# untitled.net
KiCad netlist of a schematic drawn in EAGLE
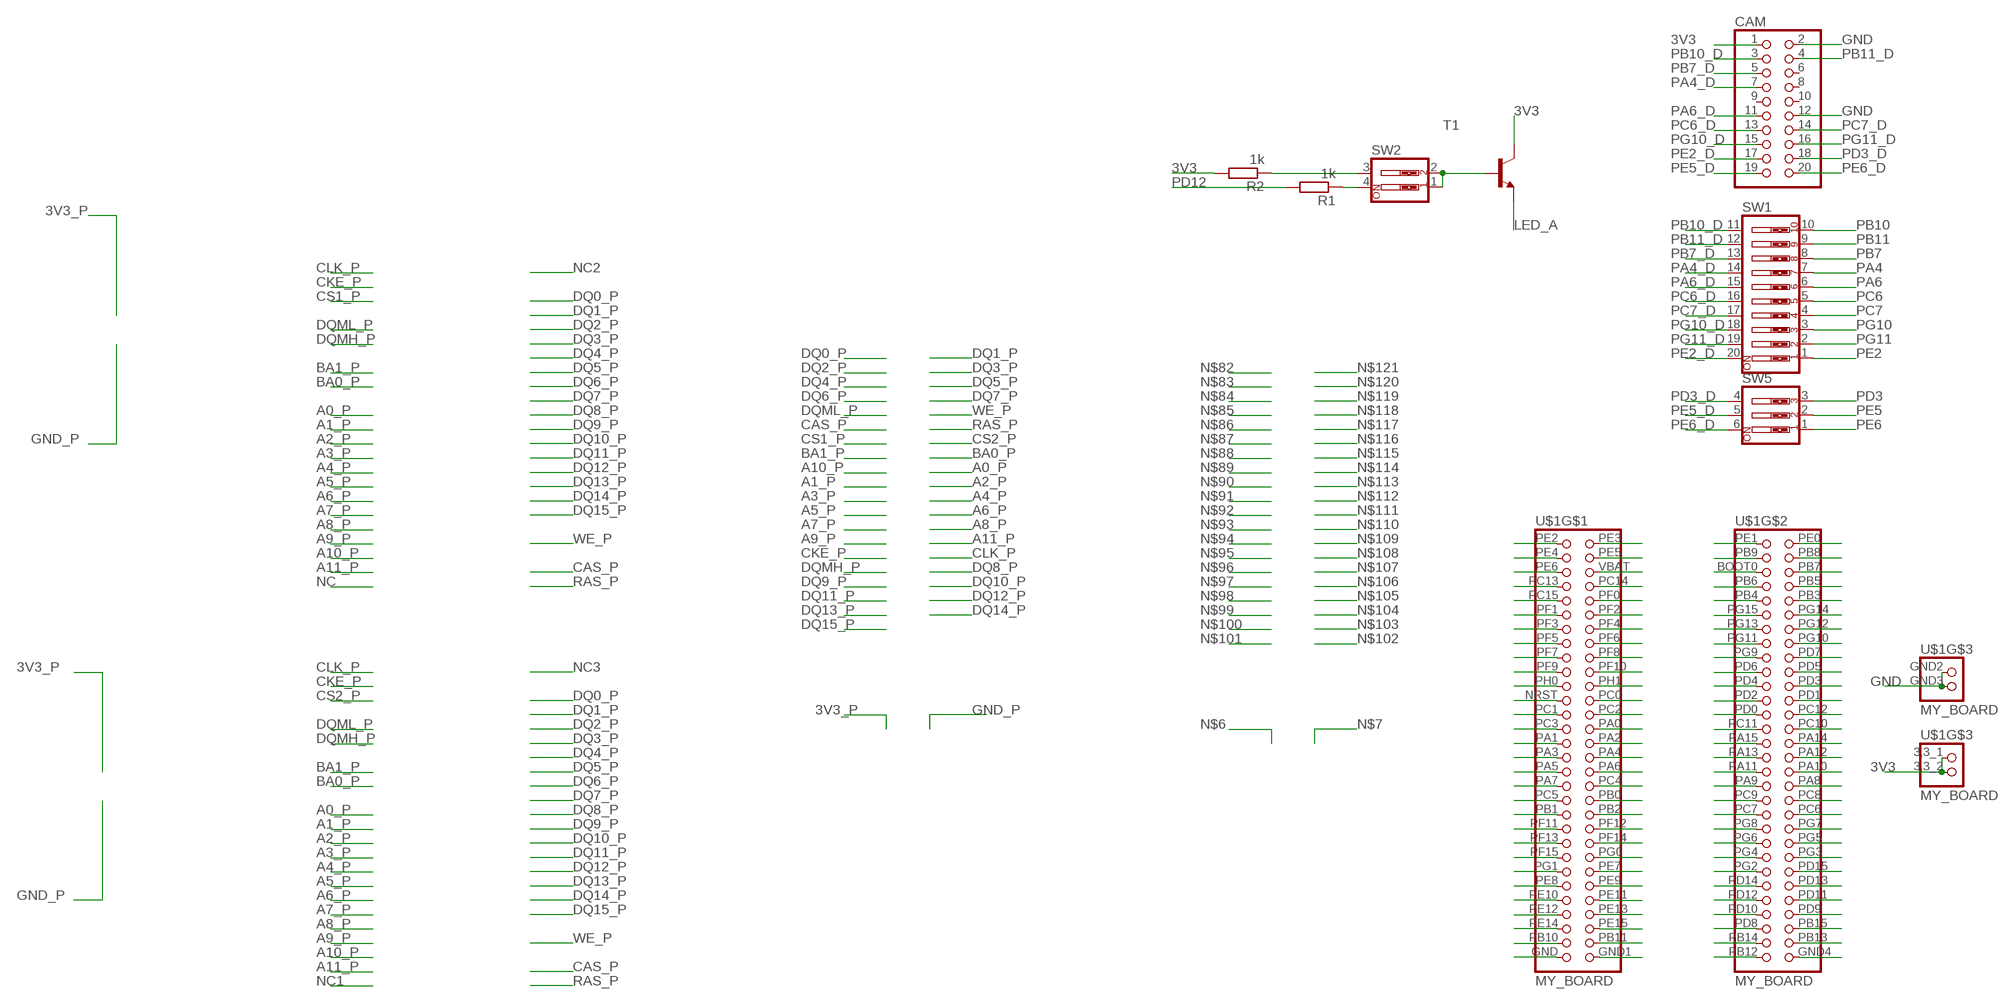
[diagram p0: schematic, sheet 1, part 1 of 2]
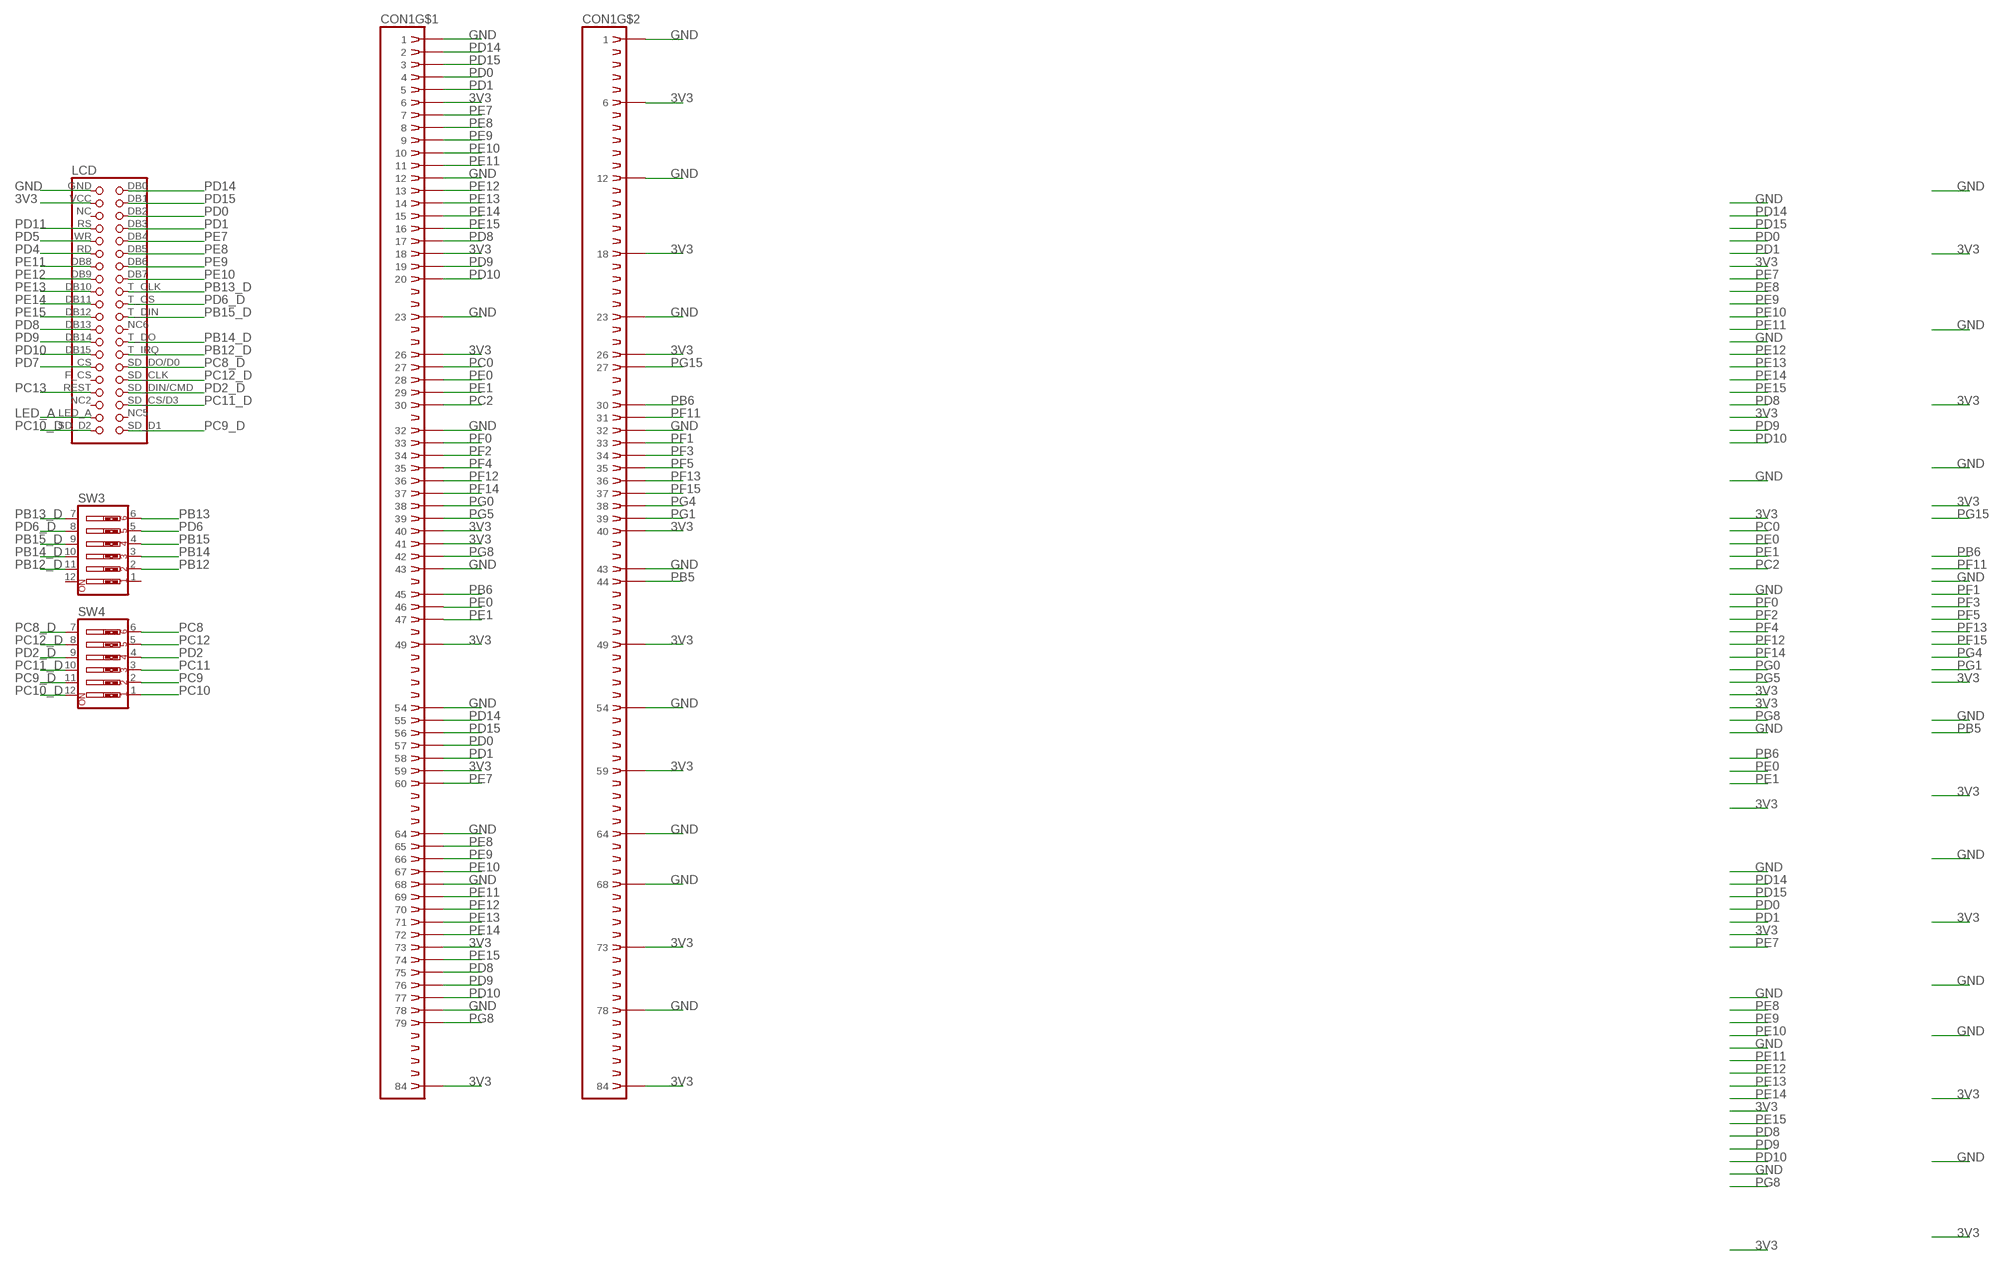
[diagram p1: schematic, sheet 1, part 2 of 2]

(export (version "E")
  (design (tool "Eeschema 10.0.6"))
  (components
    (comp (ref "CAM")
      (value "PINHD-2X10")
      (footprint "eagle-import:2X10")
      (libsource (lib "eagle-import") (part "PINHD-2X10"))
    )
    (comp (ref "CON1")
      (value "DIMM168")
      (footprint "eagle-import:390052-4")
      (libsource (lib "eagle-import") (part "DIMM168"))
    )
    (comp (ref "LCD")
      (value "LCD320QVBLCD320QVB")
      (footprint "eagle-import:2X20")
      (libsource (lib "eagle-import") (part "LCD320QVBLCD320QVB"))
    )
    (comp (ref "R1")
      (value "1k")
      (footprint "eagle-import:0204_5")
      (libsource (lib "eagle-import") (part "R-EU_0204/5"))
    )
    (comp (ref "R2")
      (value "1k")
      (footprint "eagle-import:0204_5")
      (libsource (lib "eagle-import") (part "R-EU_0204/5"))
    )
    (comp (ref "SW1")
      (value "SW_DIP-10")
      (footprint "eagle-import:EDG-10")
      (libsource (lib "eagle-import") (part "SW_DIP-10"))
    )
    (comp (ref "SW2")
      (value "SW_DIP-2")
      (footprint "eagle-import:EDG-02")
      (libsource (lib "eagle-import") (part "SW_DIP-2"))
    )
    (comp (ref "SW3")
      (value "SW_DIP-6")
      (footprint "eagle-import:EDG-06")
      (libsource (lib "eagle-import") (part "SW_DIP-6"))
    )
    (comp (ref "SW4")
      (value "SW_DIP-6")
      (footprint "eagle-import:EDG-06")
      (libsource (lib "eagle-import") (part "SW_DIP-6"))
    )
    (comp (ref "SW5")
      (value "SW_DIP-3")
      (footprint "eagle-import:EDG-03")
      (libsource (lib "eagle-import") (part "SW_DIP-3"))
    )
    (comp (ref "T1")
      (value "BC337-NPN-TO92-CBE")
      (footprint "eagle-import:TO92-CBE")
      (libsource (lib "eagle-import") (part "-NPN-TO92-CBEBC337"))
    )
    (comp (ref "U$1")
      (value "MY_BOARD")
      (footprint "eagle-import:MY_BOARD")
      (libsource (lib "eagle-import") (part "MY_BOARD"))
    )
  )
  (nets
    (net (code "1") (name "/3V3") (class "Default")
      (node (ref "CAM") (pin "1") (pinfunction "1_1") (pintype "passive"))
      (node (ref "CON1") (pin "102") (pinfunction "18_102") (pintype "passive"))
      (node (ref "CON1") (pin "110") (pinfunction "26_110") (pintype "passive"))
      (node (ref "CON1") (pin "124") (pinfunction "40_124") (pintype "passive"))
      (node (ref "CON1") (pin "133") (pinfunction "49_133") (pintype "passive"))
      (node (ref "CON1") (pin "143") (pinfunction "59_143") (pintype "passive"))
      (node (ref "CON1") (pin "157") (pinfunction "73_157") (pintype "passive"))
      (node (ref "CON1") (pin "168") (pinfunction "84_168") (pintype "passive"))
      (node (ref "CON1") (pin "18") (pinfunction "18_18") (pintype "passive"))
      (node (ref "CON1") (pin "26") (pinfunction "26_26") (pintype "passive"))
      (node (ref "CON1") (pin "40") (pinfunction "40_40") (pintype "passive"))
      (node (ref "CON1") (pin "41") (pinfunction "41_41") (pintype "passive"))
      (node (ref "CON1") (pin "49") (pinfunction "49_49") (pintype "passive"))
      (node (ref "CON1") (pin "59") (pinfunction "59_59") (pintype "passive"))
      (node (ref "CON1") (pin "6") (pinfunction "6_6") (pintype "passive"))
      (node (ref "CON1") (pin "73") (pinfunction "73_73") (pintype "passive"))
      (node (ref "CON1") (pin "84") (pinfunction "84_84") (pintype "passive"))
      (node (ref "CON1") (pin "90") (pinfunction "6_90") (pintype "passive"))
      (node (ref "LCD") (pin "VCC") (pinfunction "3_VCC") (pintype "passive"))
      (node (ref "R2") (pin "2") (pinfunction "2_2") (pintype "passive"))
      (node (ref "T1") (pin "C") (pinfunction "C_C") (pintype "passive"))
      (node (ref "U$1") (pin "3,3_1") (pinfunction "1_3,3_1") (pintype "passive"))
      (node (ref "U$1") (pin "3,3_2") (pinfunction "2_3,3_2") (pintype "passive"))
    )
    (net (code "40") (name "/GND") (class "Default")
      (node (ref "CAM") (pin "12") (pinfunction "12_12") (pintype "passive"))
      (node (ref "CAM") (pin "2") (pinfunction "2_2") (pintype "passive"))
      (node (ref "CON1") (pin "1") (pinfunction "1_1") (pintype "passive"))
      (node (ref "CON1") (pin "107") (pinfunction "23_107") (pintype "passive"))
      (node (ref "CON1") (pin "116") (pinfunction "32_116") (pintype "passive"))
      (node (ref "CON1") (pin "12") (pinfunction "12_12") (pintype "passive"))
      (node (ref "CON1") (pin "127") (pinfunction "43_127") (pintype "passive"))
      (node (ref "CON1") (pin "138") (pinfunction "54_138") (pintype "passive"))
      (node (ref "CON1") (pin "148") (pinfunction "64_148") (pintype "passive"))
      (node (ref "CON1") (pin "152") (pinfunction "68_152") (pintype "passive"))
      (node (ref "CON1") (pin "162") (pinfunction "78_162") (pintype "passive"))
      (node (ref "CON1") (pin "23") (pinfunction "23_23") (pintype "passive"))
      (node (ref "CON1") (pin "32") (pinfunction "32_32") (pintype "passive"))
      (node (ref "CON1") (pin "43") (pinfunction "43_43") (pintype "passive"))
      (node (ref "CON1") (pin "54") (pinfunction "54_54") (pintype "passive"))
      (node (ref "CON1") (pin "64") (pinfunction "64_64") (pintype "passive"))
      (node (ref "CON1") (pin "68") (pinfunction "68_68") (pintype "passive"))
      (node (ref "CON1") (pin "78") (pinfunction "78_78") (pintype "passive"))
      (node (ref "CON1") (pin "85") (pinfunction "1_85") (pintype "passive"))
      (node (ref "CON1") (pin "96") (pinfunction "12_96") (pintype "passive"))
      (node (ref "LCD") (pin "GND") (pinfunction "1_GND") (pintype "passive"))
      (node (ref "U$1") (pin "GND") (pinfunction "59_GND") (pintype "passive"))
      (node (ref "U$1") (pin "GND1") (pinfunction "60_GND1") (pintype "passive"))
      (node (ref "U$1") (pin "GND2") (pinfunction "3_GND2") (pintype "passive"))
      (node (ref "U$1") (pin "GND3") (pinfunction "4_GND3") (pintype "passive"))
      (node (ref "U$1") (pin "GND4") (pinfunction "60_GND4") (pintype "passive"))
    )
    (net (code "42") (name "/LED_A") (class "Default")
      (node (ref "LCD") (pin "LED_A") (pinfunction "37_LED_A") (pintype "passive"))
      (node (ref "T1") (pin "E") (pinfunction "E_E") (pintype "passive"))
    )
    (net (code "88") (name "/PA4") (class "Default")
      (node (ref "SW1") (pin "7") (pinfunction "7_7") (pintype "passive"))
      (node (ref "U$1") (pin "PA4") (pinfunction "32_PA4") (pintype "passive"))
    )
    (net (code "89") (name "/PA4_D") (class "Default")
      (node (ref "CAM") (pin "7") (pinfunction "7_7") (pintype "passive"))
      (node (ref "SW1") (pin "14") (pinfunction "14_14") (pintype "passive"))
    )
    (net (code "90") (name "/PA6") (class "Default")
      (node (ref "SW1") (pin "6") (pinfunction "6_6") (pintype "passive"))
      (node (ref "U$1") (pin "PA6") (pinfunction "34_PA6") (pintype "passive"))
    )
    (net (code "91") (name "/PA6_D") (class "Default")
      (node (ref "CAM") (pin "11") (pinfunction "11_11") (pintype "passive"))
      (node (ref "SW1") (pin "15") (pinfunction "15_15") (pintype "passive"))
    )
    (net (code "92") (name "/PB5") (class "Default")
      (node (ref "CON1") (pin "128") (pinfunction "44_128") (pintype "passive"))
      (node (ref "U$1") (pin "PB5") (pinfunction "8_PB5") (pintype "passive"))
    )
    (net (code "93") (name "/PB6") (class "Default")
      (node (ref "CON1") (pin "114") (pinfunction "30_114") (pintype "passive"))
      (node (ref "CON1") (pin "45") (pinfunction "45_45") (pintype "passive"))
      (node (ref "U$1") (pin "PB6") (pinfunction "7_PB6") (pintype "passive"))
    )
    (net (code "94") (name "/PB7") (class "Default")
      (node (ref "SW1") (pin "8") (pinfunction "8_8") (pintype "passive"))
      (node (ref "U$1") (pin "PB7") (pinfunction "6_PB7") (pintype "passive"))
    )
    (net (code "95") (name "/PB7_D") (class "Default")
      (node (ref "CAM") (pin "5") (pinfunction "5_5") (pintype "passive"))
      (node (ref "SW1") (pin "13") (pinfunction "13_13") (pintype "passive"))
    )
    (net (code "96") (name "/PB10") (class "Default")
      (node (ref "SW1") (pin "10") (pinfunction "10_10") (pintype "passive"))
      (node (ref "U$1") (pin "PB10") (pinfunction "57_PB10") (pintype "passive"))
    )
    (net (code "97") (name "/PB10_D") (class "Default")
      (node (ref "CAM") (pin "3") (pinfunction "3_3") (pintype "passive"))
      (node (ref "SW1") (pin "11") (pinfunction "11_11") (pintype "passive"))
    )
    (net (code "98") (name "/PB11") (class "Default")
      (node (ref "SW1") (pin "9") (pinfunction "9_9") (pintype "passive"))
      (node (ref "U$1") (pin "PB11") (pinfunction "58_PB11") (pintype "passive"))
    )
    (net (code "99") (name "/PB11_D") (class "Default")
      (node (ref "CAM") (pin "4") (pinfunction "4_4") (pintype "passive"))
      (node (ref "SW1") (pin "12") (pinfunction "12_12") (pintype "passive"))
    )
    (net (code "100") (name "/PB12") (class "Default")
      (node (ref "SW3") (pin "2") (pinfunction "2_2") (pintype "passive"))
      (node (ref "U$1") (pin "PB12") (pinfunction "59_PB12") (pintype "passive"))
    )
    (net (code "101") (name "/PB12_D") (class "Default")
      (node (ref "LCD") (pin "T_IRQ") (pinfunction "28_T_IRQ") (pintype "passive"))
      (node (ref "SW3") (pin "11") (pinfunction "11_11") (pintype "passive"))
    )
    (net (code "102") (name "/PB13") (class "Default")
      (node (ref "SW3") (pin "6") (pinfunction "6_6") (pintype "passive"))
      (node (ref "U$1") (pin "PB13") (pinfunction "58_PB13") (pintype "passive"))
    )
    (net (code "103") (name "/PB13_D") (class "Default")
      (node (ref "LCD") (pin "T_CLK") (pinfunction "18_T_CLK") (pintype "passive"))
      (node (ref "SW3") (pin "7") (pinfunction "7_7") (pintype "passive"))
    )
    (net (code "104") (name "/PB14") (class "Default")
      (node (ref "SW3") (pin "3") (pinfunction "3_3") (pintype "passive"))
      (node (ref "U$1") (pin "PB14") (pinfunction "57_PB14") (pintype "passive"))
    )
    (net (code "105") (name "/PB14_D") (class "Default")
      (node (ref "LCD") (pin "T_DO") (pinfunction "26_T_DO") (pintype "passive"))
      (node (ref "SW3") (pin "10") (pinfunction "10_10") (pintype "passive"))
    )
    (net (code "106") (name "/PB15") (class "Default")
      (node (ref "SW3") (pin "4") (pinfunction "4_4") (pintype "passive"))
      (node (ref "U$1") (pin "PB15") (pinfunction "56_PB15") (pintype "passive"))
    )
    (net (code "107") (name "/PB15_D") (class "Default")
      (node (ref "LCD") (pin "T_DIN") (pinfunction "22_T_DIN") (pintype "passive"))
      (node (ref "SW3") (pin "9") (pinfunction "9_9") (pintype "passive"))
    )
    (net (code "108") (name "/PC0") (class "Default")
      (node (ref "CON1") (pin "27") (pinfunction "27_27") (pintype "passive"))
      (node (ref "U$1") (pin "PC0") (pinfunction "24_PC0") (pintype "passive"))
    )
    (net (code "109") (name "/PC2") (class "Default")
      (node (ref "CON1") (pin "30") (pinfunction "30_30") (pintype "passive"))
      (node (ref "U$1") (pin "PC2") (pinfunction "26_PC2") (pintype "passive"))
    )
    (net (code "110") (name "/PC6") (class "Default")
      (node (ref "SW1") (pin "5") (pinfunction "5_5") (pintype "passive"))
      (node (ref "U$1") (pin "PC6") (pinfunction "40_PC6") (pintype "passive"))
    )
    (net (code "111") (name "/PC6_D") (class "Default")
      (node (ref "CAM") (pin "13") (pinfunction "13_13") (pintype "passive"))
      (node (ref "SW1") (pin "16") (pinfunction "16_16") (pintype "passive"))
    )
    (net (code "112") (name "/PC7") (class "Default")
      (node (ref "SW1") (pin "4") (pinfunction "4_4") (pintype "passive"))
      (node (ref "U$1") (pin "PC7") (pinfunction "39_PC7") (pintype "passive"))
    )
    (net (code "113") (name "/PC7_D") (class "Default")
      (node (ref "CAM") (pin "14") (pinfunction "14_14") (pintype "passive"))
      (node (ref "SW1") (pin "17") (pinfunction "17_17") (pintype "passive"))
    )
    (net (code "114") (name "/PC8") (class "Default")
      (node (ref "SW4") (pin "6") (pinfunction "6_6") (pintype "passive"))
      (node (ref "U$1") (pin "PC8") (pinfunction "38_PC8") (pintype "passive"))
    )
    (net (code "115") (name "/PC8_D") (class "Default")
      (node (ref "LCD") (pin "SD_DO/D0") (pinfunction "30_SD_DO/D0") (pintype "passive"))
      (node (ref "SW4") (pin "7") (pinfunction "7_7") (pintype "passive"))
    )
    (net (code "116") (name "/PC9") (class "Default")
      (node (ref "SW4") (pin "2") (pinfunction "2_2") (pintype "passive"))
      (node (ref "U$1") (pin "PC9") (pinfunction "37_PC9") (pintype "passive"))
    )
    (net (code "117") (name "/PC9_D") (class "Default")
      (node (ref "LCD") (pin "SD_D1") (pinfunction "40_SD_D1") (pintype "passive"))
      (node (ref "SW4") (pin "11") (pinfunction "11_11") (pintype "passive"))
    )
    (net (code "118") (name "/PC10") (class "Default")
      (node (ref "SW4") (pin "1") (pinfunction "1_1") (pintype "passive"))
      (node (ref "U$1") (pin "PC10") (pinfunction "28_PC10") (pintype "passive"))
    )
    (net (code "119") (name "/PC10_D") (class "Default")
      (node (ref "LCD") (pin "SD_D2") (pinfunction "39_SD_D2") (pintype "passive"))
      (node (ref "SW4") (pin "12") (pinfunction "12_12") (pintype "passive"))
    )
    (net (code "120") (name "/PC11") (class "Default")
      (node (ref "SW4") (pin "3") (pinfunction "3_3") (pintype "passive"))
      (node (ref "U$1") (pin "PC11") (pinfunction "27_PC11") (pintype "passive"))
    )
    (net (code "121") (name "/PC11_D") (class "Default")
      (node (ref "LCD") (pin "SD_CS/D3") (pinfunction "36_SD_CS/D3") (pintype "passive"))
      (node (ref "SW4") (pin "10") (pinfunction "10_10") (pintype "passive"))
    )
    (net (code "122") (name "/PC12") (class "Default")
      (node (ref "SW4") (pin "5") (pinfunction "5_5") (pintype "passive"))
      (node (ref "U$1") (pin "PC12") (pinfunction "26_PC12") (pintype "passive"))
    )
    (net (code "123") (name "/PC12_D") (class "Default")
      (node (ref "LCD") (pin "SD_CLK") (pinfunction "32_SD_CLK") (pintype "passive"))
      (node (ref "SW4") (pin "8") (pinfunction "8_8") (pintype "passive"))
    )
    (net (code "124") (name "/PC13") (class "Default")
      (node (ref "LCD") (pin "REST") (pinfunction "33_REST") (pintype "passive"))
      (node (ref "U$1") (pin "PC13") (pinfunction "7_PC13") (pintype "passive"))
    )
    (net (code "125") (name "/PD0") (class "Default")
      (node (ref "CON1") (pin "4") (pinfunction "4_4") (pintype "passive"))
      (node (ref "CON1") (pin "57") (pinfunction "57_57") (pintype "passive"))
      (node (ref "LCD") (pin "DB2") (pinfunction "6_DB2") (pintype "passive"))
      (node (ref "U$1") (pin "PD0") (pinfunction "25_PD0") (pintype "passive"))
    )
    (net (code "126") (name "/PD1") (class "Default")
      (node (ref "CON1") (pin "5") (pinfunction "5_5") (pintype "passive"))
      (node (ref "CON1") (pin "58") (pinfunction "58_58") (pintype "passive"))
      (node (ref "LCD") (pin "DB3") (pinfunction "8_DB3") (pintype "passive"))
      (node (ref "U$1") (pin "PD1") (pinfunction "24_PD1") (pintype "passive"))
    )
    (net (code "127") (name "/PD2") (class "Default")
      (node (ref "SW4") (pin "4") (pinfunction "4_4") (pintype "passive"))
      (node (ref "U$1") (pin "PD2") (pinfunction "23_PD2") (pintype "passive"))
    )
    (net (code "128") (name "/PD2_D") (class "Default")
      (node (ref "LCD") (pin "SD_DIN/CMD") (pinfunction "34_SD_DIN/CMD") (pintype "passive"))
      (node (ref "SW4") (pin "9") (pinfunction "9_9") (pintype "passive"))
    )
    (net (code "129") (name "/PD3") (class "Default")
      (node (ref "SW5") (pin "3") (pinfunction "3_3") (pintype "passive"))
      (node (ref "U$1") (pin "PD3") (pinfunction "22_PD3") (pintype "passive"))
    )
    (net (code "130") (name "/PD3_D") (class "Default")
      (node (ref "CAM") (pin "18") (pinfunction "18_18") (pintype "passive"))
      (node (ref "SW5") (pin "4") (pinfunction "4_4") (pintype "passive"))
    )
    (net (code "131") (name "/PD4") (class "Default")
      (node (ref "LCD") (pin "RD") (pinfunction "11_RD") (pintype "passive"))
      (node (ref "U$1") (pin "PD4") (pinfunction "21_PD4") (pintype "passive"))
    )
    (net (code "132") (name "/PD5") (class "Default")
      (node (ref "LCD") (pin "WR") (pinfunction "9_WR") (pintype "passive"))
      (node (ref "U$1") (pin "PD5") (pinfunction "20_PD5") (pintype "passive"))
    )
    (net (code "133") (name "/PD6") (class "Default")
      (node (ref "SW3") (pin "5") (pinfunction "5_5") (pintype "passive"))
      (node (ref "U$1") (pin "PD6") (pinfunction "19_PD6") (pintype "passive"))
    )
    (net (code "134") (name "/PD6_D") (class "Default")
      (node (ref "LCD") (pin "T_CS") (pinfunction "20_T_CS") (pintype "passive"))
      (node (ref "SW3") (pin "8") (pinfunction "8_8") (pintype "passive"))
    )
    (net (code "135") (name "/PD7") (class "Default")
      (node (ref "LCD") (pin "CS") (pinfunction "29_CS") (pintype "passive"))
      (node (ref "U$1") (pin "PD7") (pinfunction "18_PD7") (pintype "passive"))
    )
    (net (code "136") (name "/PD8") (class "Default")
      (node (ref "CON1") (pin "17") (pinfunction "17_17") (pintype "passive"))
      (node (ref "CON1") (pin "75") (pinfunction "75_75") (pintype "passive"))
      (node (ref "LCD") (pin "DB13") (pinfunction "23_DB13") (pintype "passive"))
      (node (ref "U$1") (pin "PD8") (pinfunction "55_PD8") (pintype "passive"))
    )
    (net (code "137") (name "/PD9") (class "Default")
      (node (ref "CON1") (pin "19") (pinfunction "19_19") (pintype "passive"))
      (node (ref "CON1") (pin "76") (pinfunction "76_76") (pintype "passive"))
      (node (ref "LCD") (pin "DB14") (pinfunction "25_DB14") (pintype "passive"))
      (node (ref "U$1") (pin "PD9") (pinfunction "54_PD9") (pintype "passive"))
    )
    (net (code "138") (name "/PD10") (class "Default")
      (node (ref "CON1") (pin "20") (pinfunction "20_20") (pintype "passive"))
      (node (ref "CON1") (pin "77") (pinfunction "77_77") (pintype "passive"))
      (node (ref "LCD") (pin "DB15") (pinfunction "27_DB15") (pintype "passive"))
      (node (ref "U$1") (pin "PD10") (pinfunction "53_PD10") (pintype "passive"))
    )
    (net (code "139") (name "/PD11") (class "Default")
      (node (ref "LCD") (pin "RS") (pinfunction "7_RS") (pintype "passive"))
      (node (ref "U$1") (pin "PD11") (pinfunction "52_PD11") (pintype "passive"))
    )
    (net (code "140") (name "/PD12") (class "Default")
      (node (ref "R1") (pin "2") (pinfunction "2_2") (pintype "passive"))
      (node (ref "U$1") (pin "PD12") (pinfunction "51_PD12") (pintype "passive"))
    )
    (net (code "141") (name "/PD14") (class "Default")
      (node (ref "CON1") (pin "2") (pinfunction "2_2") (pintype "passive"))
      (node (ref "CON1") (pin "55") (pinfunction "55_55") (pintype "passive"))
      (node (ref "LCD") (pin "DB0") (pinfunction "2_DB0") (pintype "passive"))
      (node (ref "U$1") (pin "PD14") (pinfunction "49_PD14") (pintype "passive"))
    )
    (net (code "142") (name "/PD15") (class "Default")
      (node (ref "CON1") (pin "3") (pinfunction "3_3") (pintype "passive"))
      (node (ref "CON1") (pin "56") (pinfunction "56_56") (pintype "passive"))
      (node (ref "LCD") (pin "DB1") (pinfunction "4_DB1") (pintype "passive"))
      (node (ref "U$1") (pin "PD15") (pinfunction "48_PD15") (pintype "passive"))
    )
    (net (code "143") (name "/PE0") (class "Default")
      (node (ref "CON1") (pin "28") (pinfunction "28_28") (pintype "passive"))
      (node (ref "CON1") (pin "46") (pinfunction "46_46") (pintype "passive"))
      (node (ref "U$1") (pin "PE0") (pinfunction "2_PE0") (pintype "passive"))
    )
    (net (code "144") (name "/PE1") (class "Default")
      (node (ref "CON1") (pin "29") (pinfunction "29_29") (pintype "passive"))
      (node (ref "CON1") (pin "47") (pinfunction "47_47") (pintype "passive"))
      (node (ref "U$1") (pin "PE1") (pinfunction "1_PE1") (pintype "passive"))
    )
    (net (code "145") (name "/PE2") (class "Default")
      (node (ref "SW1") (pin "1") (pinfunction "1_1") (pintype "passive"))
      (node (ref "U$1") (pin "PE2") (pinfunction "1_PE2") (pintype "passive"))
    )
    (net (code "146") (name "/PE2_D") (class "Default")
      (node (ref "CAM") (pin "17") (pinfunction "17_17") (pintype "passive"))
      (node (ref "SW1") (pin "20") (pinfunction "20_20") (pintype "passive"))
    )
    (net (code "147") (name "/PE5") (class "Default")
      (node (ref "SW5") (pin "2") (pinfunction "2_2") (pintype "passive"))
      (node (ref "U$1") (pin "PE5") (pinfunction "4_PE5") (pintype "passive"))
    )
    (net (code "148") (name "/PE5_D") (class "Default")
      (node (ref "CAM") (pin "19") (pinfunction "19_19") (pintype "passive"))
      (node (ref "SW5") (pin "5") (pinfunction "5_5") (pintype "passive"))
    )
    (net (code "149") (name "/PE6") (class "Default")
      (node (ref "SW5") (pin "1") (pinfunction "1_1") (pintype "passive"))
      (node (ref "U$1") (pin "PE6") (pinfunction "5_PE6") (pintype "passive"))
    )
    (net (code "150") (name "/PE6_D") (class "Default")
      (node (ref "CAM") (pin "20") (pinfunction "20_20") (pintype "passive"))
      (node (ref "SW5") (pin "6") (pinfunction "6_6") (pintype "passive"))
    )
    (net (code "151") (name "/PE7") (class "Default")
      (node (ref "CON1") (pin "60") (pinfunction "60_60") (pintype "passive"))
      (node (ref "CON1") (pin "7") (pinfunction "7_7") (pintype "passive"))
      (node (ref "LCD") (pin "DB4") (pinfunction "10_DB4") (pintype "passive"))
      (node (ref "U$1") (pin "PE7") (pinfunction "48_PE7") (pintype "passive"))
    )
    (net (code "152") (name "/PE8") (class "Default")
      (node (ref "CON1") (pin "65") (pinfunction "65_65") (pintype "passive"))
      (node (ref "CON1") (pin "8") (pinfunction "8_8") (pintype "passive"))
      (node (ref "LCD") (pin "DB5") (pinfunction "12_DB5") (pintype "passive"))
      (node (ref "U$1") (pin "PE8") (pinfunction "49_PE8") (pintype "passive"))
    )
    (net (code "153") (name "/PE9") (class "Default")
      (node (ref "CON1") (pin "66") (pinfunction "66_66") (pintype "passive"))
      (node (ref "CON1") (pin "9") (pinfunction "9_9") (pintype "passive"))
      (node (ref "LCD") (pin "DB6") (pinfunction "14_DB6") (pintype "passive"))
      (node (ref "U$1") (pin "PE9") (pinfunction "50_PE9") (pintype "passive"))
    )
    (net (code "154") (name "/PE10") (class "Default")
      (node (ref "CON1") (pin "10") (pinfunction "10_10") (pintype "passive"))
      (node (ref "CON1") (pin "67") (pinfunction "67_67") (pintype "passive"))
      (node (ref "LCD") (pin "DB7") (pinfunction "16_DB7") (pintype "passive"))
      (node (ref "U$1") (pin "PE10") (pinfunction "51_PE10") (pintype "passive"))
    )
    (net (code "155") (name "/PE11") (class "Default")
      (node (ref "CON1") (pin "11") (pinfunction "11_11") (pintype "passive"))
      (node (ref "CON1") (pin "69") (pinfunction "69_69") (pintype "passive"))
      (node (ref "LCD") (pin "DB8") (pinfunction "13_DB8") (pintype "passive"))
      (node (ref "U$1") (pin "PE11") (pinfunction "52_PE11") (pintype "passive"))
    )
    (net (code "156") (name "/PE12") (class "Default")
      (node (ref "CON1") (pin "13") (pinfunction "13_13") (pintype "passive"))
      (node (ref "CON1") (pin "70") (pinfunction "70_70") (pintype "passive"))
      (node (ref "LCD") (pin "DB9") (pinfunction "15_DB9") (pintype "passive"))
      (node (ref "U$1") (pin "PE12") (pinfunction "53_PE12") (pintype "passive"))
    )
    (net (code "157") (name "/PE13") (class "Default")
      (node (ref "CON1") (pin "14") (pinfunction "14_14") (pintype "passive"))
      (node (ref "CON1") (pin "71") (pinfunction "71_71") (pintype "passive"))
      (node (ref "LCD") (pin "DB10") (pinfunction "17_DB10") (pintype "passive"))
      (node (ref "U$1") (pin "PE13") (pinfunction "54_PE13") (pintype "passive"))
    )
    (net (code "158") (name "/PE14") (class "Default")
      (node (ref "CON1") (pin "15") (pinfunction "15_15") (pintype "passive"))
      (node (ref "CON1") (pin "72") (pinfunction "72_72") (pintype "passive"))
      (node (ref "LCD") (pin "DB11") (pinfunction "19_DB11") (pintype "passive"))
      (node (ref "U$1") (pin "PE14") (pinfunction "55_PE14") (pintype "passive"))
    )
    (net (code "159") (name "/PE15") (class "Default")
      (node (ref "CON1") (pin "16") (pinfunction "16_16") (pintype "passive"))
      (node (ref "CON1") (pin "74") (pinfunction "74_74") (pintype "passive"))
      (node (ref "LCD") (pin "DB12") (pinfunction "21_DB12") (pintype "passive"))
      (node (ref "U$1") (pin "PE15") (pinfunction "56_PE15") (pintype "passive"))
    )
    (net (code "160") (name "/PF0") (class "Default")
      (node (ref "CON1") (pin "33") (pinfunction "33_33") (pintype "passive"))
      (node (ref "U$1") (pin "PF0") (pinfunction "10_PF0") (pintype "passive"))
    )
    (net (code "161") (name "/PF1") (class "Default")
      (node (ref "CON1") (pin "117") (pinfunction "33_117") (pintype "passive"))
      (node (ref "U$1") (pin "PF1") (pinfunction "11_PF1") (pintype "passive"))
    )
    (net (code "162") (name "/PF2") (class "Default")
      (node (ref "CON1") (pin "34") (pinfunction "34_34") (pintype "passive"))
      (node (ref "U$1") (pin "PF2") (pinfunction "12_PF2") (pintype "passive"))
    )
    (net (code "163") (name "/PF3") (class "Default")
      (node (ref "CON1") (pin "118") (pinfunction "34_118") (pintype "passive"))
      (node (ref "U$1") (pin "PF3") (pinfunction "13_PF3") (pintype "passive"))
    )
    (net (code "164") (name "/PF4") (class "Default")
      (node (ref "CON1") (pin "35") (pinfunction "35_35") (pintype "passive"))
      (node (ref "U$1") (pin "PF4") (pinfunction "14_PF4") (pintype "passive"))
    )
    (net (code "165") (name "/PF5") (class "Default")
      (node (ref "CON1") (pin "119") (pinfunction "35_119") (pintype "passive"))
      (node (ref "U$1") (pin "PF5") (pinfunction "15_PF5") (pintype "passive"))
    )
    (net (code "166") (name "/PF11") (class "Default")
      (node (ref "CON1") (pin "115") (pinfunction "31_115") (pintype "passive"))
      (node (ref "U$1") (pin "PF11") (pinfunction "41_PF11") (pintype "passive"))
    )
    (net (code "167") (name "/PF12") (class "Default")
      (node (ref "CON1") (pin "36") (pinfunction "36_36") (pintype "passive"))
      (node (ref "U$1") (pin "PF12") (pinfunction "42_PF12") (pintype "passive"))
    )
    (net (code "168") (name "/PF13") (class "Default")
      (node (ref "CON1") (pin "120") (pinfunction "36_120") (pintype "passive"))
      (node (ref "U$1") (pin "PF13") (pinfunction "43_PF13") (pintype "passive"))
    )
    (net (code "169") (name "/PF14") (class "Default")
      (node (ref "CON1") (pin "37") (pinfunction "37_37") (pintype "passive"))
      (node (ref "U$1") (pin "PF14") (pinfunction "44_PF14") (pintype "passive"))
    )
    (net (code "170") (name "/PF15") (class "Default")
      (node (ref "CON1") (pin "121") (pinfunction "37_121") (pintype "passive"))
      (node (ref "U$1") (pin "PF15") (pinfunction "45_PF15") (pintype "passive"))
    )
    (net (code "171") (name "/PG0") (class "Default")
      (node (ref "CON1") (pin "38") (pinfunction "38_38") (pintype "passive"))
      (node (ref "U$1") (pin "PG0") (pinfunction "46_PG0") (pintype "passive"))
    )
    (net (code "172") (name "/PG1") (class "Default")
      (node (ref "CON1") (pin "123") (pinfunction "39_123") (pintype "passive"))
      (node (ref "U$1") (pin "PG1") (pinfunction "47_PG1") (pintype "passive"))
    )
    (net (code "173") (name "/PG4") (class "Default")
      (node (ref "CON1") (pin "122") (pinfunction "38_122") (pintype "passive"))
      (node (ref "U$1") (pin "PG4") (pinfunction "45_PG4") (pintype "passive"))
    )
    (net (code "174") (name "/PG5") (class "Default")
      (node (ref "CON1") (pin "39") (pinfunction "39_39") (pintype "passive"))
      (node (ref "U$1") (pin "PG5") (pinfunction "44_PG5") (pintype "passive"))
    )
    (net (code "175") (name "/PG8") (class "Default")
      (node (ref "CON1") (pin "42") (pinfunction "42_42") (pintype "passive"))
      (node (ref "CON1") (pin "79") (pinfunction "79_79") (pintype "passive"))
      (node (ref "U$1") (pin "PG8") (pinfunction "41_PG8") (pintype "passive"))
    )
    (net (code "176") (name "/PG10") (class "Default")
      (node (ref "SW1") (pin "3") (pinfunction "3_3") (pintype "passive"))
      (node (ref "U$1") (pin "PG10") (pinfunction "16_PG10") (pintype "passive"))
    )
    (net (code "177") (name "/PG10_D") (class "Default")
      (node (ref "CAM") (pin "15") (pinfunction "15_15") (pintype "passive"))
      (node (ref "SW1") (pin "18") (pinfunction "18_18") (pintype "passive"))
    )
    (net (code "178") (name "/PG11") (class "Default")
      (node (ref "SW1") (pin "2") (pinfunction "2_2") (pintype "passive"))
      (node (ref "U$1") (pin "PG11") (pinfunction "15_PG11") (pintype "passive"))
    )
    (net (code "179") (name "/PG11_D") (class "Default")
      (node (ref "CAM") (pin "16") (pinfunction "16_16") (pintype "passive"))
      (node (ref "SW1") (pin "19") (pinfunction "19_19") (pintype "passive"))
    )
    (net (code "180") (name "/PG15") (class "Default")
      (node (ref "CON1") (pin "111") (pinfunction "27_111") (pintype "passive"))
      (node (ref "U$1") (pin "PG15") (pinfunction "11_PG15") (pintype "passive"))
    )
    (net (code "183") (name "Net-(R1-Pad1)") (class "Default")
      (node (ref "R1") (pin "1") (pinfunction "1_1") (pintype "passive"))
      (node (ref "SW2") (pin "4") (pinfunction "4_4") (pintype "passive"))
    )
    (net (code "184") (name "Net-(R2-Pad1)") (class "Default")
      (node (ref "R2") (pin "1") (pinfunction "1_1") (pintype "passive"))
      (node (ref "SW2") (pin "3") (pinfunction "3_3") (pintype "passive"))
    )
    (net (code "185") (name "Net-(SW2-Pad1)") (class "Default")
      (node (ref "SW2") (pin "1") (pinfunction "1_1") (pintype "passive"))
      (node (ref "SW2") (pin "2") (pinfunction "2_2") (pintype "passive"))
      (node (ref "T1") (pin "B") (pinfunction "B_B") (pintype "passive"))
    )
    (net (code "186") (name "unconnected-(CAM-Pad6)") (class "Default")
      (node (ref "CAM") (pin "6") (pinfunction "6_6") (pintype "passive"))
    )
    (net (code "187") (name "unconnected-(CAM-Pad8)") (class "Default")
      (node (ref "CAM") (pin "8") (pinfunction "8_8") (pintype "passive"))
    )
    (net (code "188") (name "unconnected-(CAM-Pad9)") (class "Default")
      (node (ref "CAM") (pin "9") (pinfunction "9_9") (pintype "passive"))
    )
    (net (code "189") (name "unconnected-(CAM-Pad10)") (class "Default")
      (node (ref "CAM") (pin "10") (pinfunction "10_10") (pintype "passive"))
    )
    (net (code "190") (name "unconnected-(LCD-5-PadNC)") (class "Default")
      (node (ref "LCD") (pin "NC") (pinfunction "5_NC") (pintype "passive"))
    )
    (net (code "191") (name "unconnected-(LCD-24-PadNC6)") (class "Default")
      (node (ref "LCD") (pin "NC6") (pinfunction "24_NC6") (pintype "passive"))
    )
    (net (code "192") (name "unconnected-(LCD-31-PadF_CS)") (class "Default")
      (node (ref "LCD") (pin "F_CS") (pinfunction "31_F_CS") (pintype "passive"))
    )
    (net (code "193") (name "unconnected-(LCD-35-PadNC2)") (class "Default")
      (node (ref "LCD") (pin "NC2") (pinfunction "35_NC2") (pintype "passive"))
    )
    (net (code "194") (name "unconnected-(LCD-38-PadNC5)") (class "Default")
      (node (ref "LCD") (pin "NC5") (pinfunction "38_NC5") (pintype "passive"))
    )
    (net (code "195") (name "unconnected-(SW3-Pad1)") (class "Default")
      (node (ref "SW3") (pin "1") (pinfunction "1_1") (pintype "passive"))
    )
    (net (code "196") (name "unconnected-(SW3-Pad12)") (class "Default")
      (node (ref "SW3") (pin "12") (pinfunction "12_12") (pintype "passive"))
    )
    (net (code "197") (name "unconnected-(U$1A-2-PadPE3)") (class "Default")
      (node (ref "U$1") (pin "PE3") (pinfunction "2_PE3") (pintype "passive"))
    )
    (net (code "198") (name "unconnected-(U$1A-3-PadPE4)") (class "Default")
      (node (ref "U$1") (pin "PE4") (pinfunction "3_PE4") (pintype "passive"))
    )
    (net (code "199") (name "unconnected-(U$1A-6-PadVBAT)") (class "Default")
      (node (ref "U$1") (pin "VBAT") (pinfunction "6_VBAT") (pintype "passive"))
    )
    (net (code "200") (name "unconnected-(U$1A-8-PadPC14)") (class "Default")
      (node (ref "U$1") (pin "PC14") (pinfunction "8_PC14") (pintype "passive"))
    )
    (net (code "201") (name "unconnected-(U$1A-9-PadPC15)") (class "Default")
      (node (ref "U$1") (pin "PC15") (pinfunction "9_PC15") (pintype "passive"))
    )
    (net (code "202") (name "unconnected-(U$1A-16-PadPF6)") (class "Default")
      (node (ref "U$1") (pin "PF6") (pinfunction "16_PF6") (pintype "passive"))
    )
    (net (code "203") (name "unconnected-(U$1A-17-PadPF7)") (class "Default")
      (node (ref "U$1") (pin "PF7") (pinfunction "17_PF7") (pintype "passive"))
    )
    (net (code "204") (name "unconnected-(U$1A-18-PadPF8)") (class "Default")
      (node (ref "U$1") (pin "PF8") (pinfunction "18_PF8") (pintype "passive"))
    )
    (net (code "205") (name "unconnected-(U$1A-19-PadPF9)") (class "Default")
      (node (ref "U$1") (pin "PF9") (pinfunction "19_PF9") (pintype "passive"))
    )
    (net (code "206") (name "unconnected-(U$1A-20-PadPF10)") (class "Default")
      (node (ref "U$1") (pin "PF10") (pinfunction "20_PF10") (pintype "passive"))
    )
    (net (code "207") (name "unconnected-(U$1A-21-PadPH0)") (class "Default")
      (node (ref "U$1") (pin "PH0") (pinfunction "21_PH0") (pintype "passive"))
    )
    (net (code "208") (name "unconnected-(U$1A-22-PadPH1)") (class "Default")
      (node (ref "U$1") (pin "PH1") (pinfunction "22_PH1") (pintype "passive"))
    )
    (net (code "209") (name "unconnected-(U$1A-23-PadNRST)") (class "Default")
      (node (ref "U$1") (pin "NRST") (pinfunction "23_NRST") (pintype "passive"))
    )
    (net (code "210") (name "unconnected-(U$1A-25-PadPC1)") (class "Default")
      (node (ref "U$1") (pin "PC1") (pinfunction "25_PC1") (pintype "passive"))
    )
    (net (code "211") (name "unconnected-(U$1A-27-PadPC3)") (class "Default")
      (node (ref "U$1") (pin "PC3") (pinfunction "27_PC3") (pintype "passive"))
    )
    (net (code "212") (name "unconnected-(U$1A-28-PadPA0)") (class "Default")
      (node (ref "U$1") (pin "PA0") (pinfunction "28_PA0") (pintype "passive"))
    )
    (net (code "213") (name "unconnected-(U$1A-29-PadPA1)") (class "Default")
      (node (ref "U$1") (pin "PA1") (pinfunction "29_PA1") (pintype "passive"))
    )
    (net (code "214") (name "unconnected-(U$1A-30-PadPA2)") (class "Default")
      (node (ref "U$1") (pin "PA2") (pinfunction "30_PA2") (pintype "passive"))
    )
    (net (code "215") (name "unconnected-(U$1A-31-PadPA3)") (class "Default")
      (node (ref "U$1") (pin "PA3") (pinfunction "31_PA3") (pintype "passive"))
    )
    (net (code "216") (name "unconnected-(U$1A-33-PadPA5)") (class "Default")
      (node (ref "U$1") (pin "PA5") (pinfunction "33_PA5") (pintype "passive"))
    )
    (net (code "217") (name "unconnected-(U$1A-35-PadPA7)") (class "Default")
      (node (ref "U$1") (pin "PA7") (pinfunction "35_PA7") (pintype "passive"))
    )
    (net (code "218") (name "unconnected-(U$1A-36-PadPC4)") (class "Default")
      (node (ref "U$1") (pin "PC4") (pinfunction "36_PC4") (pintype "passive"))
    )
    (net (code "219") (name "unconnected-(U$1A-37-PadPC5)") (class "Default")
      (node (ref "U$1") (pin "PC5") (pinfunction "37_PC5") (pintype "passive"))
    )
    (net (code "220") (name "unconnected-(U$1A-38-PadPB0)") (class "Default")
      (node (ref "U$1") (pin "PB0") (pinfunction "38_PB0") (pintype "passive"))
    )
    (net (code "221") (name "unconnected-(U$1A-39-PadPB1)") (class "Default")
      (node (ref "U$1") (pin "PB1") (pinfunction "39_PB1") (pintype "passive"))
    )
    (net (code "222") (name "unconnected-(U$1A-40-PadPB2)") (class "Default")
      (node (ref "U$1") (pin "PB2") (pinfunction "40_PB2") (pintype "passive"))
    )
    (net (code "223") (name "unconnected-(U$1B-3-PadPB9)") (class "Default")
      (node (ref "U$1") (pin "PB9") (pinfunction "3_PB9") (pintype "passive"))
    )
    (net (code "224") (name "unconnected-(U$1B-4-PadPB8)") (class "Default")
      (node (ref "U$1") (pin "PB8") (pinfunction "4_PB8") (pintype "passive"))
    )
    (net (code "225") (name "unconnected-(U$1B-5-PadBOOT0)") (class "Default")
      (node (ref "U$1") (pin "BOOT0") (pinfunction "5_BOOT0") (pintype "passive"))
    )
    (net (code "226") (name "unconnected-(U$1B-9-PadPB4)") (class "Default")
      (node (ref "U$1") (pin "PB4") (pinfunction "9_PB4") (pintype "passive"))
    )
    (net (code "227") (name "unconnected-(U$1B-10-PadPB3)") (class "Default")
      (node (ref "U$1") (pin "PB3") (pinfunction "10_PB3") (pintype "passive"))
    )
    (net (code "228") (name "unconnected-(U$1B-12-PadPG14)") (class "Default")
      (node (ref "U$1") (pin "PG14") (pinfunction "12_PG14") (pintype "passive"))
    )
    (net (code "229") (name "unconnected-(U$1B-13-PadPG13)") (class "Default")
      (node (ref "U$1") (pin "PG13") (pinfunction "13_PG13") (pintype "passive"))
    )
    (net (code "230") (name "unconnected-(U$1B-14-PadPG12)") (class "Default")
      (node (ref "U$1") (pin "PG12") (pinfunction "14_PG12") (pintype "passive"))
    )
    (net (code "231") (name "unconnected-(U$1B-17-PadPG9)") (class "Default")
      (node (ref "U$1") (pin "PG9") (pinfunction "17_PG9") (pintype "passive"))
    )
    (net (code "232") (name "unconnected-(U$1B-29-PadPA15)") (class "Default")
      (node (ref "U$1") (pin "PA15") (pinfunction "29_PA15") (pintype "passive"))
    )
    (net (code "233") (name "unconnected-(U$1B-30-PadPA14)") (class "Default")
      (node (ref "U$1") (pin "PA14") (pinfunction "30_PA14") (pintype "passive"))
    )
    (net (code "234") (name "unconnected-(U$1B-31-PadPA13)") (class "Default")
      (node (ref "U$1") (pin "PA13") (pinfunction "31_PA13") (pintype "passive"))
    )
    (net (code "235") (name "unconnected-(U$1B-32-PadPA12)") (class "Default")
      (node (ref "U$1") (pin "PA12") (pinfunction "32_PA12") (pintype "passive"))
    )
    (net (code "236") (name "unconnected-(U$1B-33-PadPA11)") (class "Default")
      (node (ref "U$1") (pin "PA11") (pinfunction "33_PA11") (pintype "passive"))
    )
    (net (code "237") (name "unconnected-(U$1B-34-PadPA10)") (class "Default")
      (node (ref "U$1") (pin "PA10") (pinfunction "34_PA10") (pintype "passive"))
    )
    (net (code "238") (name "unconnected-(U$1B-35-PadPA9)") (class "Default")
      (node (ref "U$1") (pin "PA9") (pinfunction "35_PA9") (pintype "passive"))
    )
    (net (code "239") (name "unconnected-(U$1B-36-PadPA8)") (class "Default")
      (node (ref "U$1") (pin "PA8") (pinfunction "36_PA8") (pintype "passive"))
    )
    (net (code "240") (name "unconnected-(U$1B-42-PadPG7)") (class "Default")
      (node (ref "U$1") (pin "PG7") (pinfunction "42_PG7") (pintype "passive"))
    )
    (net (code "241") (name "unconnected-(U$1B-43-PadPG6)") (class "Default")
      (node (ref "U$1") (pin "PG6") (pinfunction "43_PG6") (pintype "passive"))
    )
    (net (code "242") (name "unconnected-(U$1B-46-PadPG3)") (class "Default")
      (node (ref "U$1") (pin "PG3") (pinfunction "46_PG3") (pintype "passive"))
    )
    (net (code "243") (name "unconnected-(U$1B-47-PadPG2)") (class "Default")
      (node (ref "U$1") (pin "PG2") (pinfunction "47_PG2") (pintype "passive"))
    )
    (net (code "244") (name "unconnected-(U$1B-50-PadPD13)") (class "Default")
      (node (ref "U$1") (pin "PD13") (pinfunction "50_PD13") (pintype "passive"))
    )
  )
)
